# h-bridge_mosfets_ver_AB.net
KiCad netlist of a schematic drawn in EAGLE
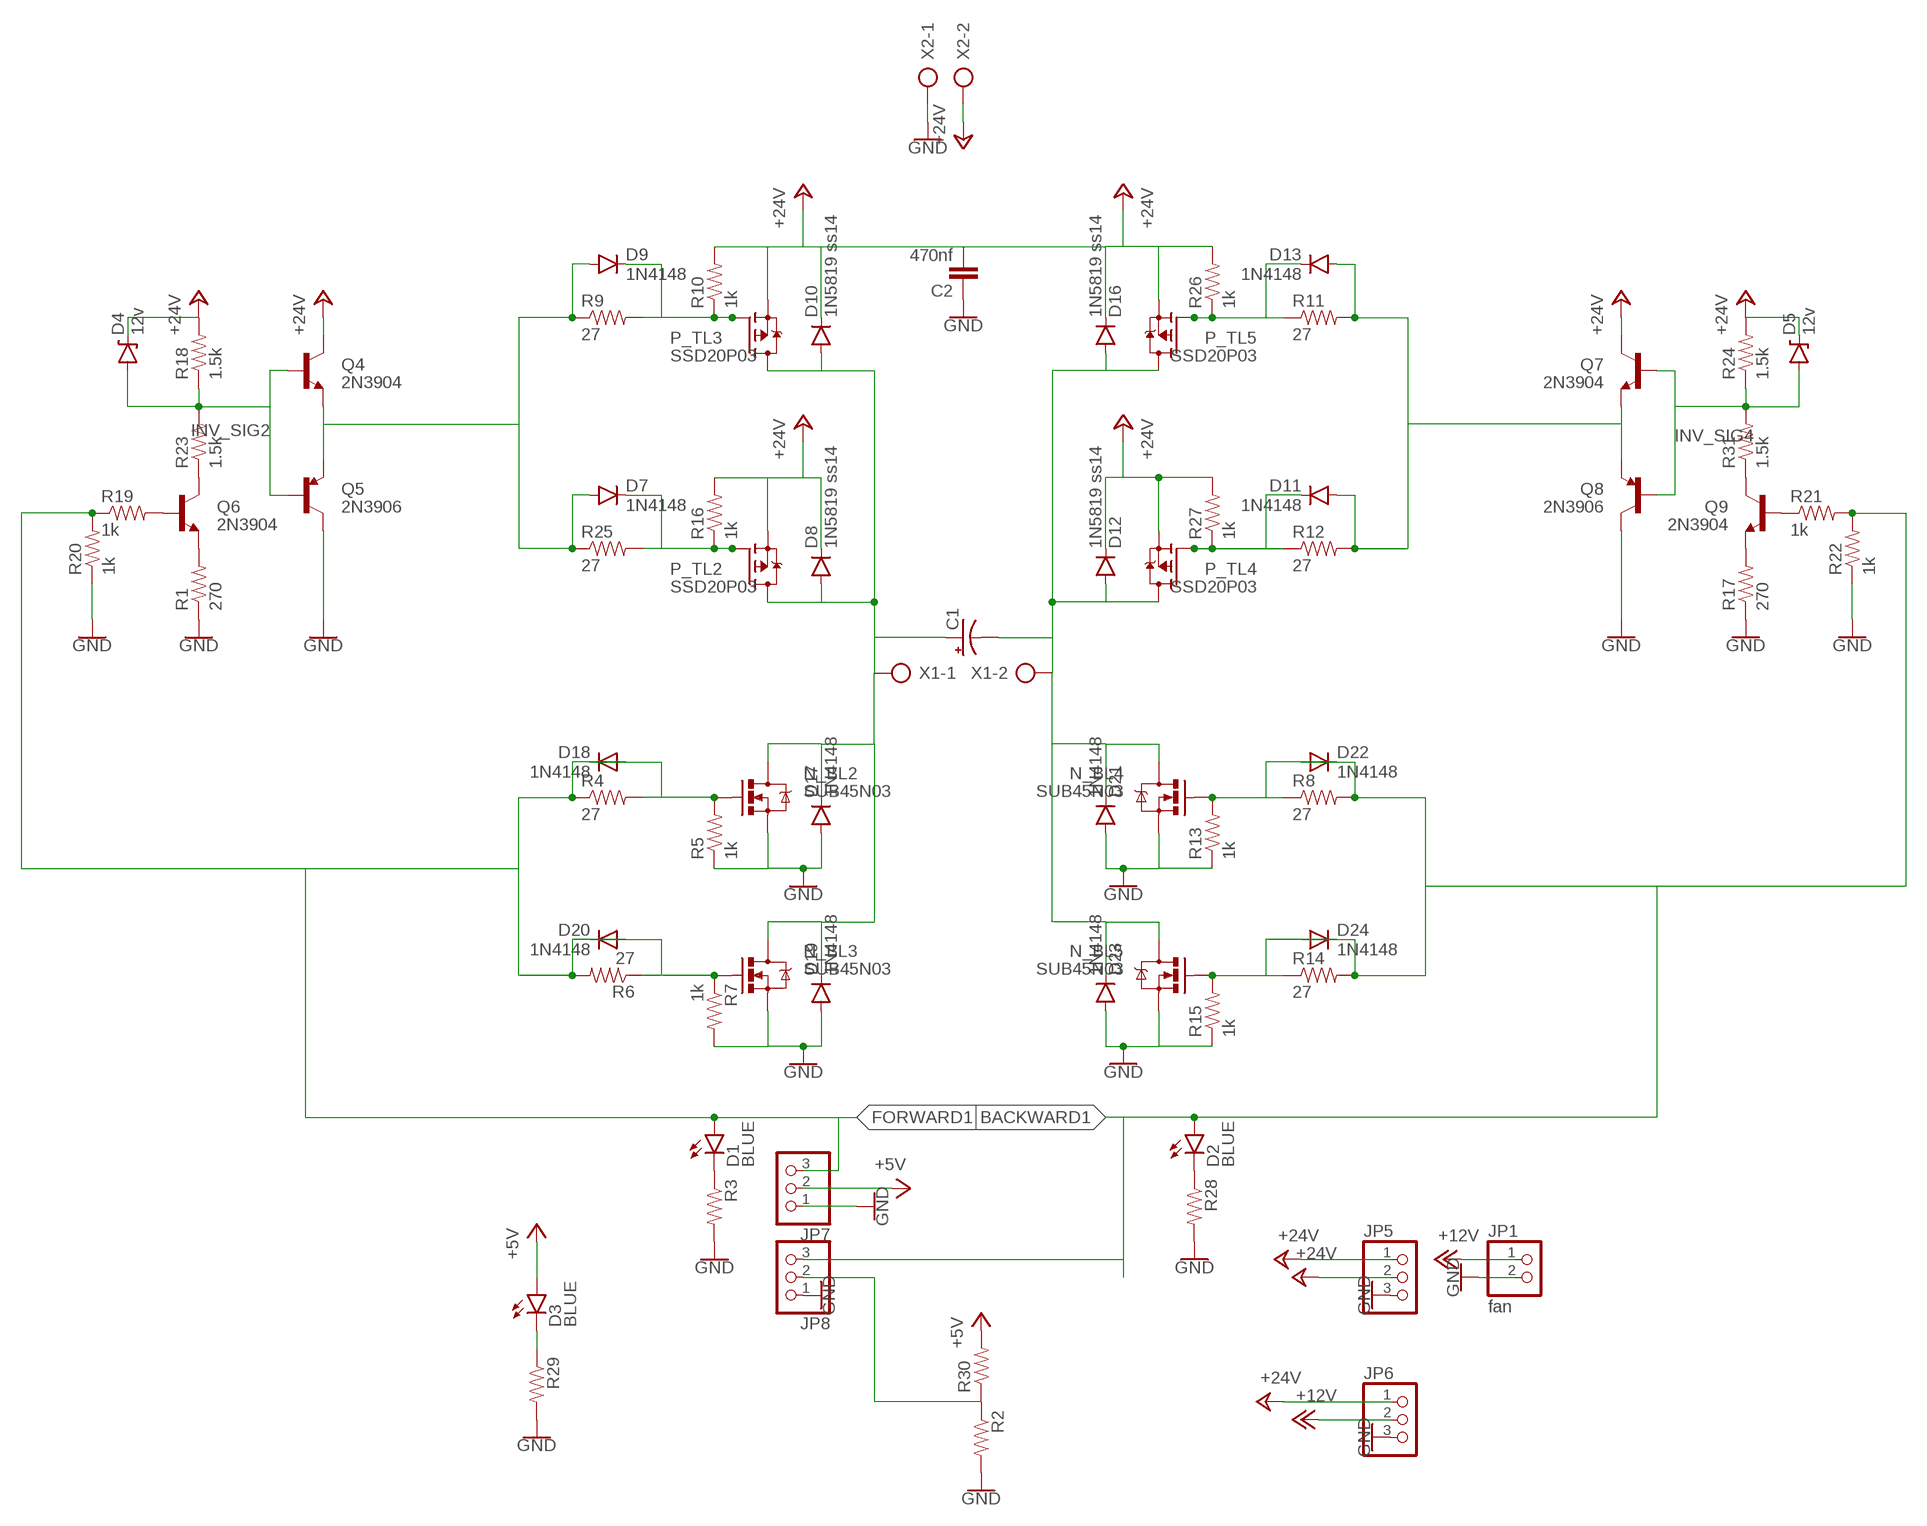
[diagram p0: schematic, sheet 1]

(export (version "E")
  (design (tool "Eeschema 10.0.6"))
  (components
    (comp (ref "C1")
      (value "1000UF-25V(PTH)")
      (footprint "eagle-import:CPOL-RADIAL-1000UF-25V")
      (libsource (lib "eagle-import") (part "1000UF-25V(PTH)"))
    )
    (comp (ref "C2")
      (value "470nf")
      (footprint "eagle-import:1206")
      (libsource (lib "eagle-import") (part "1.0UF50V10%(1206)"))
    )
    (comp (ref "D1")
      (value "BLUE")
      (footprint "eagle-import:LED-1206")
      (libsource (lib "eagle-import") (part "LED-BLUE1206"))
    )
    (comp (ref "D2")
      (value "BLUE")
      (footprint "eagle-import:LED-1206")
      (libsource (lib "eagle-import") (part "LED-BLUE1206"))
    )
    (comp (ref "D3")
      (value "BLUE")
      (footprint "eagle-import:LED-1206")
      (libsource (lib "eagle-import") (part "LED-BLUE1206"))
    )
    (comp (ref "D4")
      (value "12v")
      (footprint "eagle-import:SMB-DIODE")
      (libsource (lib "eagle-import") (part "DIODE-ZENERSMB"))
    )
    (comp (ref "D5")
      (value "12v")
      (footprint "eagle-import:SMB-DIODE")
      (libsource (lib "eagle-import") (part "DIODE-ZENERSMB"))
    )
    (comp (ref "D7")
      (value "1N4148")
      (footprint "eagle-import:SOD-123")
      (libsource (lib "eagle-import") (part "DIODESOD123"))
    )
    (comp (ref "D8")
      (value "1N5819 ss14")
      (footprint "eagle-import:SOD-123")
      (libsource (lib "eagle-import") (part "DIODESOD123"))
    )
    (comp (ref "D9")
      (value "1N4148")
      (footprint "eagle-import:SOD-123")
      (libsource (lib "eagle-import") (part "DIODESOD123"))
    )
    (comp (ref "D10")
      (value "1N5819 ss14")
      (footprint "eagle-import:SOD-123")
      (libsource (lib "eagle-import") (part "DIODESOD123"))
    )
    (comp (ref "D11")
      (value "1N4148")
      (footprint "eagle-import:SOD-123")
      (libsource (lib "eagle-import") (part "DIODESOD123"))
    )
    (comp (ref "D12")
      (value "1N5819 ss14")
      (footprint "eagle-import:SOD-123")
      (libsource (lib "eagle-import") (part "DIODESOD123"))
    )
    (comp (ref "D13")
      (value "1N4148")
      (footprint "eagle-import:SOD-123")
      (libsource (lib "eagle-import") (part "DIODESOD123"))
    )
    (comp (ref "D16")
      (value "1N5819 ss14")
      (footprint "eagle-import:SOD-123")
      (libsource (lib "eagle-import") (part "DIODESOD123"))
    )
    (comp (ref "D17")
      (value "1N4148")
      (footprint "eagle-import:SOD-123")
      (libsource (lib "eagle-import") (part "DIODESOD123"))
    )
    (comp (ref "D18")
      (value "1N4148")
      (footprint "eagle-import:SOD-123")
      (libsource (lib "eagle-import") (part "DIODESOD123"))
    )
    (comp (ref "D19")
      (value "1N4148")
      (footprint "eagle-import:SOD-123")
      (libsource (lib "eagle-import") (part "DIODESOD123"))
    )
    (comp (ref "D20")
      (value "1N4148")
      (footprint "eagle-import:SOD-123")
      (libsource (lib "eagle-import") (part "DIODESOD123"))
    )
    (comp (ref "D21")
      (value "1N4148")
      (footprint "eagle-import:SOD-123")
      (libsource (lib "eagle-import") (part "DIODESOD123"))
    )
    (comp (ref "D22")
      (value "1N4148")
      (footprint "eagle-import:SOD-123")
      (libsource (lib "eagle-import") (part "DIODESOD123"))
    )
    (comp (ref "D23")
      (value "1N4148")
      (footprint "eagle-import:SOD-123")
      (libsource (lib "eagle-import") (part "DIODESOD123"))
    )
    (comp (ref "D24")
      (value "1N4148")
      (footprint "eagle-import:SOD-123")
      (libsource (lib "eagle-import") (part "DIODESOD123"))
    )
    (comp (ref "JP1")
      (value "fan")
      (footprint "eagle-import:1X02")
      (libsource (lib "eagle-import") (part "PINHD-1X2"))
    )
    (comp (ref "JP5")
      (value "PINHD-1X3")
      (footprint "eagle-import:1X03")
      (libsource (lib "eagle-import") (part "PINHD-1X3"))
    )
    (comp (ref "JP6")
      (value "PINHD-1X3")
      (footprint "eagle-import:1X03")
      (libsource (lib "eagle-import") (part "PINHD-1X3"))
    )
    (comp (ref "JP7")
      (value "PINHD-1X3")
      (footprint "eagle-import:1X03")
      (libsource (lib "eagle-import") (part "PINHD-1X3"))
    )
    (comp (ref "JP8")
      (value "PINHD-1X3")
      (footprint "eagle-import:1X03")
      (libsource (lib "eagle-import") (part "PINHD-1X3"))
    )
    (comp (ref "N_BL2")
      (value "SUB45N03")
      (footprint "eagle-import:TO-263_D2PAK")
      (libsource (lib "eagle-import") (part "MOSFET-NCHANNELPSMN7R0"))
    )
    (comp (ref "N_BL3")
      (value "SUB45N03")
      (footprint "eagle-import:TO-263_D2PAK")
      (libsource (lib "eagle-import") (part "MOSFET-NCHANNELPSMN7R0"))
    )
    (comp (ref "N_BL4")
      (value "SUB45N03")
      (footprint "eagle-import:TO-263_D2PAK")
      (libsource (lib "eagle-import") (part "MOSFET-NCHANNELPSMN7R0"))
    )
    (comp (ref "N_BL5")
      (value "SUB45N03")
      (footprint "eagle-import:TO-263_D2PAK")
      (libsource (lib "eagle-import") (part "MOSFET-NCHANNELPSMN7R0"))
    )
    (comp (ref "P_TL2")
      (value "SSD20P03")
      (footprint "eagle-import:TO252")
      (libsource (lib "eagle-import") (part "FDD4141TO252"))
    )
    (comp (ref "P_TL3")
      (value "SSD20P03")
      (footprint "eagle-import:TO252")
      (libsource (lib "eagle-import") (part "FDD4141TO252"))
    )
    (comp (ref "P_TL4")
      (value "SSD20P03")
      (footprint "eagle-import:TO252")
      (libsource (lib "eagle-import") (part "FDD4141TO252"))
    )
    (comp (ref "P_TL5")
      (value "SSD20P03")
      (footprint "eagle-import:TO252")
      (libsource (lib "eagle-import") (part "FDD4141TO252"))
    )
    (comp (ref "Q4")
      (value "2N3904")
      (footprint "eagle-import:SOT23-3")
      (libsource (lib "eagle-import") (part "TRANSISTOR_NPNMMBT5088"))
    )
    (comp (ref "Q5")
      (value "2N3906")
      (footprint "eagle-import:SOT23-3")
      (libsource (lib "eagle-import") (part "TRANSISTOR_PNPPMBT3906"))
    )
    (comp (ref "Q6")
      (value "2N3904")
      (footprint "eagle-import:SOT23-3")
      (libsource (lib "eagle-import") (part "TRANSISTOR_NPNMMBT5088"))
    )
    (comp (ref "Q7")
      (value "2N3904")
      (footprint "eagle-import:SOT23-3")
      (libsource (lib "eagle-import") (part "TRANSISTOR_NPNMMBT5088"))
    )
    (comp (ref "Q8")
      (value "2N3906")
      (footprint "eagle-import:SOT23-3")
      (libsource (lib "eagle-import") (part "TRANSISTOR_PNPPMBT3906"))
    )
    (comp (ref "Q9")
      (value "2N3904")
      (footprint "eagle-import:SOT23-3")
      (libsource (lib "eagle-import") (part "TRANSISTOR_NPNMMBT5088"))
    )
    (comp (ref "R1")
      (value "270")
      (footprint "eagle-import:0805")
      (libsource (lib "eagle-import") (part "0.3OHM-1/8W-1%(0805)"))
    )
    (comp (ref "R2")
      (value "0.3OHM-1/8W-1%(0805)")
      (footprint "eagle-import:0805")
      (libsource (lib "eagle-import") (part "0.3OHM-1/8W-1%(0805)"))
    )
    (comp (ref "R3")
      (value "0.3OHM-1/8W-1%(0805)")
      (footprint "eagle-import:0805")
      (libsource (lib "eagle-import") (part "0.3OHM-1/8W-1%(0805)"))
    )
    (comp (ref "R4")
      (value "27")
      (footprint "eagle-import:0805")
      (libsource (lib "eagle-import") (part "0.3OHM-1/8W-1%(0805)"))
    )
    (comp (ref "R5")
      (value "1k")
      (footprint "eagle-import:0805")
      (libsource (lib "eagle-import") (part "0.3OHM-1/8W-1%(0805)"))
    )
    (comp (ref "R6")
      (value "27")
      (footprint "eagle-import:0805")
      (libsource (lib "eagle-import") (part "0.3OHM-1/8W-1%(0805)"))
    )
    (comp (ref "R7")
      (value "1k")
      (footprint "eagle-import:0805")
      (libsource (lib "eagle-import") (part "0.3OHM-1/8W-1%(0805)"))
    )
    (comp (ref "R8")
      (value "27")
      (footprint "eagle-import:0805")
      (libsource (lib "eagle-import") (part "0.3OHM-1/8W-1%(0805)"))
    )
    (comp (ref "R9")
      (value "27")
      (footprint "eagle-import:0805")
      (libsource (lib "eagle-import") (part "0.3OHM-1/8W-1%(0805)"))
    )
    (comp (ref "R10")
      (value "1k")
      (footprint "eagle-import:0805")
      (libsource (lib "eagle-import") (part "0.3OHM-1/8W-1%(0805)"))
    )
    (comp (ref "R11")
      (value "27")
      (footprint "eagle-import:0805")
      (libsource (lib "eagle-import") (part "0.3OHM-1/8W-1%(0805)"))
    )
    (comp (ref "R12")
      (value "27")
      (footprint "eagle-import:0805")
      (libsource (lib "eagle-import") (part "0.3OHM-1/8W-1%(0805)"))
    )
    (comp (ref "R13")
      (value "1k")
      (footprint "eagle-import:0805")
      (libsource (lib "eagle-import") (part "0.3OHM-1/8W-1%(0805)"))
    )
    (comp (ref "R14")
      (value "27")
      (footprint "eagle-import:0805")
      (libsource (lib "eagle-import") (part "0.3OHM-1/8W-1%(0805)"))
    )
    (comp (ref "R15")
      (value "1k")
      (footprint "eagle-import:0805")
      (libsource (lib "eagle-import") (part "0.3OHM-1/8W-1%(0805)"))
    )
    (comp (ref "R16")
      (value "1k")
      (footprint "eagle-import:0805")
      (libsource (lib "eagle-import") (part "0.3OHM-1/8W-1%(0805)"))
    )
    (comp (ref "R17")
      (value "270")
      (footprint "eagle-import:0805")
      (libsource (lib "eagle-import") (part "0.3OHM-1/8W-1%(0805)"))
    )
    (comp (ref "R18")
      (value "1.5k")
      (footprint "eagle-import:0805")
      (libsource (lib "eagle-import") (part "0.3OHM-1/8W-1%(0805)"))
    )
    (comp (ref "R19")
      (value "1k")
      (footprint "eagle-import:0805")
      (libsource (lib "eagle-import") (part "0.3OHM-1/8W-1%(0805)"))
    )
    (comp (ref "R20")
      (value "1k")
      (footprint "eagle-import:0805")
      (libsource (lib "eagle-import") (part "0.3OHM-1/8W-1%(0805)"))
    )
    (comp (ref "R21")
      (value "1k")
      (footprint "eagle-import:0805")
      (libsource (lib "eagle-import") (part "0.3OHM-1/8W-1%(0805)"))
    )
    (comp (ref "R22")
      (value "1k")
      (footprint "eagle-import:0805")
      (libsource (lib "eagle-import") (part "0.3OHM-1/8W-1%(0805)"))
    )
    (comp (ref "R23")
      (value "1.5k")
      (footprint "eagle-import:0805")
      (libsource (lib "eagle-import") (part "0.3OHM-1/8W-1%(0805)"))
    )
    (comp (ref "R24")
      (value "1.5k")
      (footprint "eagle-import:0805")
      (libsource (lib "eagle-import") (part "0.3OHM-1/8W-1%(0805)"))
    )
    (comp (ref "R25")
      (value "27")
      (footprint "eagle-import:0805")
      (libsource (lib "eagle-import") (part "0.3OHM-1/8W-1%(0805)"))
    )
    (comp (ref "R26")
      (value "1k")
      (footprint "eagle-import:0805")
      (libsource (lib "eagle-import") (part "0.3OHM-1/8W-1%(0805)"))
    )
    (comp (ref "R27")
      (value "1k")
      (footprint "eagle-import:0805")
      (libsource (lib "eagle-import") (part "0.3OHM-1/8W-1%(0805)"))
    )
    (comp (ref "R28")
      (value "0.3OHM-1/8W-1%(0805)")
      (footprint "eagle-import:0805")
      (libsource (lib "eagle-import") (part "0.3OHM-1/8W-1%(0805)"))
    )
    (comp (ref "R29")
      (value "0.3OHM-1/8W-1%(0805)")
      (footprint "eagle-import:0805")
      (libsource (lib "eagle-import") (part "0.3OHM-1/8W-1%(0805)"))
    )
    (comp (ref "R30")
      (value "RESISTORPTH-1/4W-VERT-KIT")
      (footprint "eagle-import:AXIAL-0.1EZ")
      (libsource (lib "eagle-import") (part "RESISTORPTH-1/4W-VERT-KIT"))
    )
    (comp (ref "R31")
      (value "1.5k")
      (footprint "eagle-import:0805")
      (libsource (lib "eagle-import") (part "0.3OHM-1/8W-1%(0805)"))
    )
    (comp (ref "X1")
      (value "AK300/2")
      (footprint "eagle-import:AK300_2")
      (libsource (lib "eagle-import") (part "AK300/2"))
    )
    (comp (ref "X2")
      (value "AK300/2")
      (footprint "eagle-import:AK300_2")
      (libsource (lib "eagle-import") (part "AK300/2"))
    )
  )
  (nets
    (net (code "1") (name "+5V") (class "Default")
      (node (ref "D3") (pin "A") (pinfunction "A_A") (pintype "passive"))
      (node (ref "JP7") (pin "2") (pinfunction "2_2") (pintype "passive"))
      (node (ref "R30") (pin "P$2") (pinfunction "2_P$2") (pintype "passive"))
    )
    (net (code "2") (name "+12V") (class "Default")
      (node (ref "JP1") (pin "1") (pinfunction "1_1") (pintype "passive"))
      (node (ref "JP6") (pin "2") (pinfunction "2_2") (pintype "passive"))
    )
    (net (code "3") (name "+24V") (class "Default")
      (node (ref "C2") (pin "2") (pinfunction "2_2") (pintype "passive"))
      (node (ref "D10") (pin "C") (pinfunction "C_C") (pintype "passive"))
      (node (ref "D12") (pin "C") (pinfunction "C_C") (pintype "passive"))
      (node (ref "D16") (pin "C") (pinfunction "C_C") (pintype "passive"))
      (node (ref "D4") (pin "C") (pinfunction "C_C") (pintype "passive"))
      (node (ref "D5") (pin "C") (pinfunction "C_C") (pintype "passive"))
      (node (ref "D8") (pin "C") (pinfunction "C_C") (pintype "passive"))
      (node (ref "JP5") (pin "1") (pinfunction "1_1") (pintype "passive"))
      (node (ref "JP5") (pin "2") (pinfunction "2_2") (pintype "passive"))
      (node (ref "JP6") (pin "1") (pinfunction "1_1") (pintype "passive"))
      (node (ref "P_TL2") (pin "2") (pinfunction "S_2") (pintype "passive"))
      (node (ref "P_TL3") (pin "2") (pinfunction "S_2") (pintype "passive"))
      (node (ref "P_TL4") (pin "2") (pinfunction "S_2") (pintype "passive"))
      (node (ref "P_TL5") (pin "2") (pinfunction "S_2") (pintype "passive"))
      (node (ref "Q4") (pin "3") (pinfunction "C_3") (pintype "passive"))
      (node (ref "Q7") (pin "3") (pinfunction "C_3") (pintype "passive"))
      (node (ref "R10") (pin "2") (pinfunction "2_2") (pintype "passive"))
      (node (ref "R16") (pin "2") (pinfunction "2_2") (pintype "passive"))
      (node (ref "R18") (pin "2") (pinfunction "2_2") (pintype "passive"))
      (node (ref "R24") (pin "2") (pinfunction "2_2") (pintype "passive"))
      (node (ref "R26") (pin "2") (pinfunction "2_2") (pintype "passive"))
      (node (ref "R27") (pin "2") (pinfunction "2_2") (pintype "passive"))
      (node (ref "X2") (pin "2") (pinfunction "KL_2") (pintype "passive"))
    )
    (net (code "4") (name "/INV_SIG2") (class "Default")
      (node (ref "D4") (pin "A") (pinfunction "A_A") (pintype "passive"))
      (node (ref "Q4") (pin "1") (pinfunction "B_1") (pintype "passive"))
      (node (ref "Q5") (pin "1") (pinfunction "B_1") (pintype "passive"))
      (node (ref "R18") (pin "1") (pinfunction "1_1") (pintype "passive"))
      (node (ref "R23") (pin "2") (pinfunction "2_2") (pintype "passive"))
    )
    (net (code "5") (name "/INV_SIG4") (class "Default")
      (node (ref "D5") (pin "A") (pinfunction "A_A") (pintype "passive"))
      (node (ref "Q7") (pin "1") (pinfunction "B_1") (pintype "passive"))
      (node (ref "Q8") (pin "1") (pinfunction "B_1") (pintype "passive"))
      (node (ref "R24") (pin "1") (pinfunction "1_1") (pintype "passive"))
      (node (ref "R31") (pin "2") (pinfunction "2_2") (pintype "passive"))
    )
    (net (code "6") (name "BACKWARD1") (class "Default")
      (node (ref "D2") (pin "A") (pinfunction "A_A") (pintype "passive"))
      (node (ref "D22") (pin "A") (pinfunction "A_A") (pintype "passive"))
      (node (ref "D24") (pin "A") (pinfunction "A_A") (pintype "passive"))
      (node (ref "JP8") (pin "3") (pinfunction "3_3") (pintype "passive"))
      (node (ref "R14") (pin "2") (pinfunction "2_2") (pintype "passive"))
      (node (ref "R21") (pin "2") (pinfunction "2_2") (pintype "passive"))
      (node (ref "R22") (pin "2") (pinfunction "2_2") (pintype "passive"))
      (node (ref "R8") (pin "2") (pinfunction "2_2") (pintype "passive"))
    )
    (net (code "7") (name "FORWARD1") (class "Default")
      (node (ref "D1") (pin "A") (pinfunction "A_A") (pintype "passive"))
      (node (ref "D18") (pin "A") (pinfunction "A_A") (pintype "passive"))
      (node (ref "D20") (pin "A") (pinfunction "A_A") (pintype "passive"))
      (node (ref "JP7") (pin "3") (pinfunction "3_3") (pintype "passive"))
      (node (ref "R19") (pin "1") (pinfunction "1_1") (pintype "passive"))
      (node (ref "R20") (pin "2") (pinfunction "2_2") (pintype "passive"))
      (node (ref "R4") (pin "1") (pinfunction "1_1") (pintype "passive"))
      (node (ref "R6") (pin "2") (pinfunction "2_2") (pintype "passive"))
    )
    (net (code "8") (name "GND") (class "Default")
      (node (ref "C2") (pin "1") (pinfunction "1_1") (pintype "passive"))
      (node (ref "D17") (pin "A") (pinfunction "A_A") (pintype "passive"))
      (node (ref "D19") (pin "A") (pinfunction "A_A") (pintype "passive"))
      (node (ref "D21") (pin "A") (pinfunction "A_A") (pintype "passive"))
      (node (ref "D23") (pin "A") (pinfunction "A_A") (pintype "passive"))
      (node (ref "JP1") (pin "2") (pinfunction "2_2") (pintype "passive"))
      (node (ref "JP5") (pin "3") (pinfunction "3_3") (pintype "passive"))
      (node (ref "JP6") (pin "3") (pinfunction "3_3") (pintype "passive"))
      (node (ref "JP7") (pin "1") (pinfunction "1_1") (pintype "passive"))
      (node (ref "JP8") (pin "1") (pinfunction "1_1") (pintype "passive"))
      (node (ref "N_BL2") (pin "3") (pinfunction "S_3") (pintype "passive"))
      (node (ref "N_BL3") (pin "3") (pinfunction "S_3") (pintype "passive"))
      (node (ref "N_BL4") (pin "3") (pinfunction "S_3") (pintype "passive"))
      (node (ref "N_BL5") (pin "3") (pinfunction "S_3") (pintype "passive"))
      (node (ref "Q5") (pin "3") (pinfunction "C_3") (pintype "passive"))
      (node (ref "Q8") (pin "3") (pinfunction "C_3") (pintype "passive"))
      (node (ref "R1") (pin "1") (pinfunction "1_1") (pintype "passive"))
      (node (ref "R13") (pin "1") (pinfunction "1_1") (pintype "passive"))
      (node (ref "R15") (pin "1") (pinfunction "1_1") (pintype "passive"))
      (node (ref "R17") (pin "1") (pinfunction "1_1") (pintype "passive"))
      (node (ref "R2") (pin "2") (pinfunction "2_2") (pintype "passive"))
      (node (ref "R20") (pin "1") (pinfunction "1_1") (pintype "passive"))
      (node (ref "R22") (pin "1") (pinfunction "1_1") (pintype "passive"))
      (node (ref "R28") (pin "2") (pinfunction "2_2") (pintype "passive"))
      (node (ref "R29") (pin "2") (pinfunction "2_2") (pintype "passive"))
      (node (ref "R3") (pin "2") (pinfunction "2_2") (pintype "passive"))
      (node (ref "R5") (pin "1") (pinfunction "1_1") (pintype "passive"))
      (node (ref "R7") (pin "2") (pinfunction "2_2") (pintype "passive"))
      (node (ref "X2") (pin "1") (pinfunction "KL_1") (pintype "passive"))
    )
    (net (code "9") (name "Net-(D1-PadC)") (class "Default")
      (node (ref "D1") (pin "C") (pinfunction "C_C") (pintype "passive"))
      (node (ref "R3") (pin "1") (pinfunction "1_1") (pintype "passive"))
    )
    (net (code "10") (name "Net-(D2-PadC)") (class "Default")
      (node (ref "D2") (pin "C") (pinfunction "C_C") (pintype "passive"))
      (node (ref "R28") (pin "1") (pinfunction "1_1") (pintype "passive"))
    )
    (net (code "11") (name "Net-(D3-PadC)") (class "Default")
      (node (ref "D3") (pin "C") (pinfunction "C_C") (pintype "passive"))
      (node (ref "R29") (pin "1") (pinfunction "1_1") (pintype "passive"))
    )
    (net (code "12") (name "Net-(N_BL2-D)") (class "Default")
      (node (ref "C1") (pin "+") (pinfunction "+_+") (pintype "passive"))
      (node (ref "D10") (pin "A") (pinfunction "A_A") (pintype "passive"))
      (node (ref "D17") (pin "C") (pinfunction "C_C") (pintype "passive"))
      (node (ref "D19") (pin "C") (pinfunction "C_C") (pintype "passive"))
      (node (ref "D8") (pin "A") (pinfunction "A_A") (pintype "passive"))
      (node (ref "N_BL2") (pin "2") (pinfunction "D_2") (pintype "passive"))
      (node (ref "N_BL3") (pin "2") (pinfunction "D_2") (pintype "passive"))
      (node (ref "P_TL2") (pin "3") (pinfunction "D_3") (pintype "passive"))
      (node (ref "P_TL3") (pin "3") (pinfunction "D_3") (pintype "passive"))
      (node (ref "X1") (pin "1") (pinfunction "KL_1") (pintype "passive"))
    )
    (net (code "13") (name "Net-(N_BL2-G)") (class "Default")
      (node (ref "D18") (pin "C") (pinfunction "C_C") (pintype "passive"))
      (node (ref "N_BL2") (pin "1") (pinfunction "G_1") (pintype "passive"))
      (node (ref "R4") (pin "2") (pinfunction "2_2") (pintype "passive"))
      (node (ref "R5") (pin "2") (pinfunction "2_2") (pintype "passive"))
    )
    (net (code "14") (name "Net-(N_BL3-G)") (class "Default")
      (node (ref "D20") (pin "C") (pinfunction "C_C") (pintype "passive"))
      (node (ref "N_BL3") (pin "1") (pinfunction "G_1") (pintype "passive"))
      (node (ref "R6") (pin "1") (pinfunction "1_1") (pintype "passive"))
      (node (ref "R7") (pin "1") (pinfunction "1_1") (pintype "passive"))
    )
    (net (code "15") (name "Net-(N_BL4-D)") (class "Default")
      (node (ref "C1") (pin "-") (pinfunction "-_-") (pintype "passive"))
      (node (ref "D12") (pin "A") (pinfunction "A_A") (pintype "passive"))
      (node (ref "D16") (pin "A") (pinfunction "A_A") (pintype "passive"))
      (node (ref "D21") (pin "C") (pinfunction "C_C") (pintype "passive"))
      (node (ref "D23") (pin "C") (pinfunction "C_C") (pintype "passive"))
      (node (ref "N_BL4") (pin "2") (pinfunction "D_2") (pintype "passive"))
      (node (ref "N_BL5") (pin "2") (pinfunction "D_2") (pintype "passive"))
      (node (ref "P_TL4") (pin "3") (pinfunction "D_3") (pintype "passive"))
      (node (ref "P_TL5") (pin "3") (pinfunction "D_3") (pintype "passive"))
      (node (ref "X1") (pin "2") (pinfunction "KL_2") (pintype "passive"))
    )
    (net (code "16") (name "Net-(N_BL4-G)") (class "Default")
      (node (ref "D22") (pin "C") (pinfunction "C_C") (pintype "passive"))
      (node (ref "N_BL4") (pin "1") (pinfunction "G_1") (pintype "passive"))
      (node (ref "R13") (pin "2") (pinfunction "2_2") (pintype "passive"))
      (node (ref "R8") (pin "1") (pinfunction "1_1") (pintype "passive"))
    )
    (net (code "17") (name "Net-(N_BL5-G)") (class "Default")
      (node (ref "D24") (pin "C") (pinfunction "C_C") (pintype "passive"))
      (node (ref "N_BL5") (pin "1") (pinfunction "G_1") (pintype "passive"))
      (node (ref "R14") (pin "1") (pinfunction "1_1") (pintype "passive"))
      (node (ref "R15") (pin "2") (pinfunction "2_2") (pintype "passive"))
    )
    (net (code "18") (name "Net-(P_TL2-G)") (class "Default")
      (node (ref "D7") (pin "C") (pinfunction "C_C") (pintype "passive"))
      (node (ref "P_TL2") (pin "1") (pinfunction "G_1") (pintype "passive"))
      (node (ref "R16") (pin "1") (pinfunction "1_1") (pintype "passive"))
      (node (ref "R25") (pin "2") (pinfunction "2_2") (pintype "passive"))
    )
    (net (code "19") (name "Net-(P_TL3-G)") (class "Default")
      (node (ref "D9") (pin "C") (pinfunction "C_C") (pintype "passive"))
      (node (ref "P_TL3") (pin "1") (pinfunction "G_1") (pintype "passive"))
      (node (ref "R10") (pin "1") (pinfunction "1_1") (pintype "passive"))
      (node (ref "R9") (pin "2") (pinfunction "2_2") (pintype "passive"))
    )
    (net (code "20") (name "Net-(P_TL4-G)") (class "Default")
      (node (ref "D11") (pin "C") (pinfunction "C_C") (pintype "passive"))
      (node (ref "P_TL4") (pin "1") (pinfunction "G_1") (pintype "passive"))
      (node (ref "R12") (pin "1") (pinfunction "1_1") (pintype "passive"))
      (node (ref "R27") (pin "1") (pinfunction "1_1") (pintype "passive"))
    )
    (net (code "21") (name "Net-(P_TL5-G)") (class "Default")
      (node (ref "D13") (pin "C") (pinfunction "C_C") (pintype "passive"))
      (node (ref "P_TL5") (pin "1") (pinfunction "G_1") (pintype "passive"))
      (node (ref "R11") (pin "1") (pinfunction "1_1") (pintype "passive"))
      (node (ref "R26") (pin "1") (pinfunction "1_1") (pintype "passive"))
    )
    (net (code "22") (name "Net-(Q4-E)") (class "Default")
      (node (ref "D7") (pin "A") (pinfunction "A_A") (pintype "passive"))
      (node (ref "D9") (pin "A") (pinfunction "A_A") (pintype "passive"))
      (node (ref "Q4") (pin "2") (pinfunction "E_2") (pintype "passive"))
      (node (ref "Q5") (pin "2") (pinfunction "E_2") (pintype "passive"))
      (node (ref "R25") (pin "1") (pinfunction "1_1") (pintype "passive"))
      (node (ref "R9") (pin "1") (pinfunction "1_1") (pintype "passive"))
    )
    (net (code "23") (name "Net-(Q6-B)") (class "Default")
      (node (ref "Q6") (pin "1") (pinfunction "B_1") (pintype "passive"))
      (node (ref "R19") (pin "2") (pinfunction "2_2") (pintype "passive"))
    )
    (net (code "24") (name "Net-(Q6-C)") (class "Default")
      (node (ref "Q6") (pin "3") (pinfunction "C_3") (pintype "passive"))
      (node (ref "R23") (pin "1") (pinfunction "1_1") (pintype "passive"))
    )
    (net (code "25") (name "Net-(Q6-E)") (class "Default")
      (node (ref "Q6") (pin "2") (pinfunction "E_2") (pintype "passive"))
      (node (ref "R1") (pin "2") (pinfunction "2_2") (pintype "passive"))
    )
    (net (code "26") (name "Net-(Q7-E)") (class "Default")
      (node (ref "D11") (pin "A") (pinfunction "A_A") (pintype "passive"))
      (node (ref "D13") (pin "A") (pinfunction "A_A") (pintype "passive"))
      (node (ref "Q7") (pin "2") (pinfunction "E_2") (pintype "passive"))
      (node (ref "Q8") (pin "2") (pinfunction "E_2") (pintype "passive"))
      (node (ref "R11") (pin "2") (pinfunction "2_2") (pintype "passive"))
      (node (ref "R12") (pin "2") (pinfunction "2_2") (pintype "passive"))
    )
    (net (code "27") (name "Net-(Q9-B)") (class "Default")
      (node (ref "Q9") (pin "1") (pinfunction "B_1") (pintype "passive"))
      (node (ref "R21") (pin "1") (pinfunction "1_1") (pintype "passive"))
    )
    (net (code "28") (name "Net-(Q9-C)") (class "Default")
      (node (ref "Q9") (pin "3") (pinfunction "C_3") (pintype "passive"))
      (node (ref "R31") (pin "1") (pinfunction "1_1") (pintype "passive"))
    )
    (net (code "29") (name "Net-(Q9-E)") (class "Default")
      (node (ref "Q9") (pin "2") (pinfunction "E_2") (pintype "passive"))
      (node (ref "R17") (pin "2") (pinfunction "2_2") (pintype "passive"))
    )
    (net (code "30") (name "Net-(R30-1)") (class "Default")
      (node (ref "JP8") (pin "2") (pinfunction "2_2") (pintype "passive"))
      (node (ref "R2") (pin "1") (pinfunction "1_1") (pintype "passive"))
      (node (ref "R30") (pin "P$1") (pinfunction "1_P$1") (pintype "passive"))
    )
  )
)
